# Volta-Interface-SCH_SH2__A.net
KiCad netlist of a schematic drawn in Altium Designer
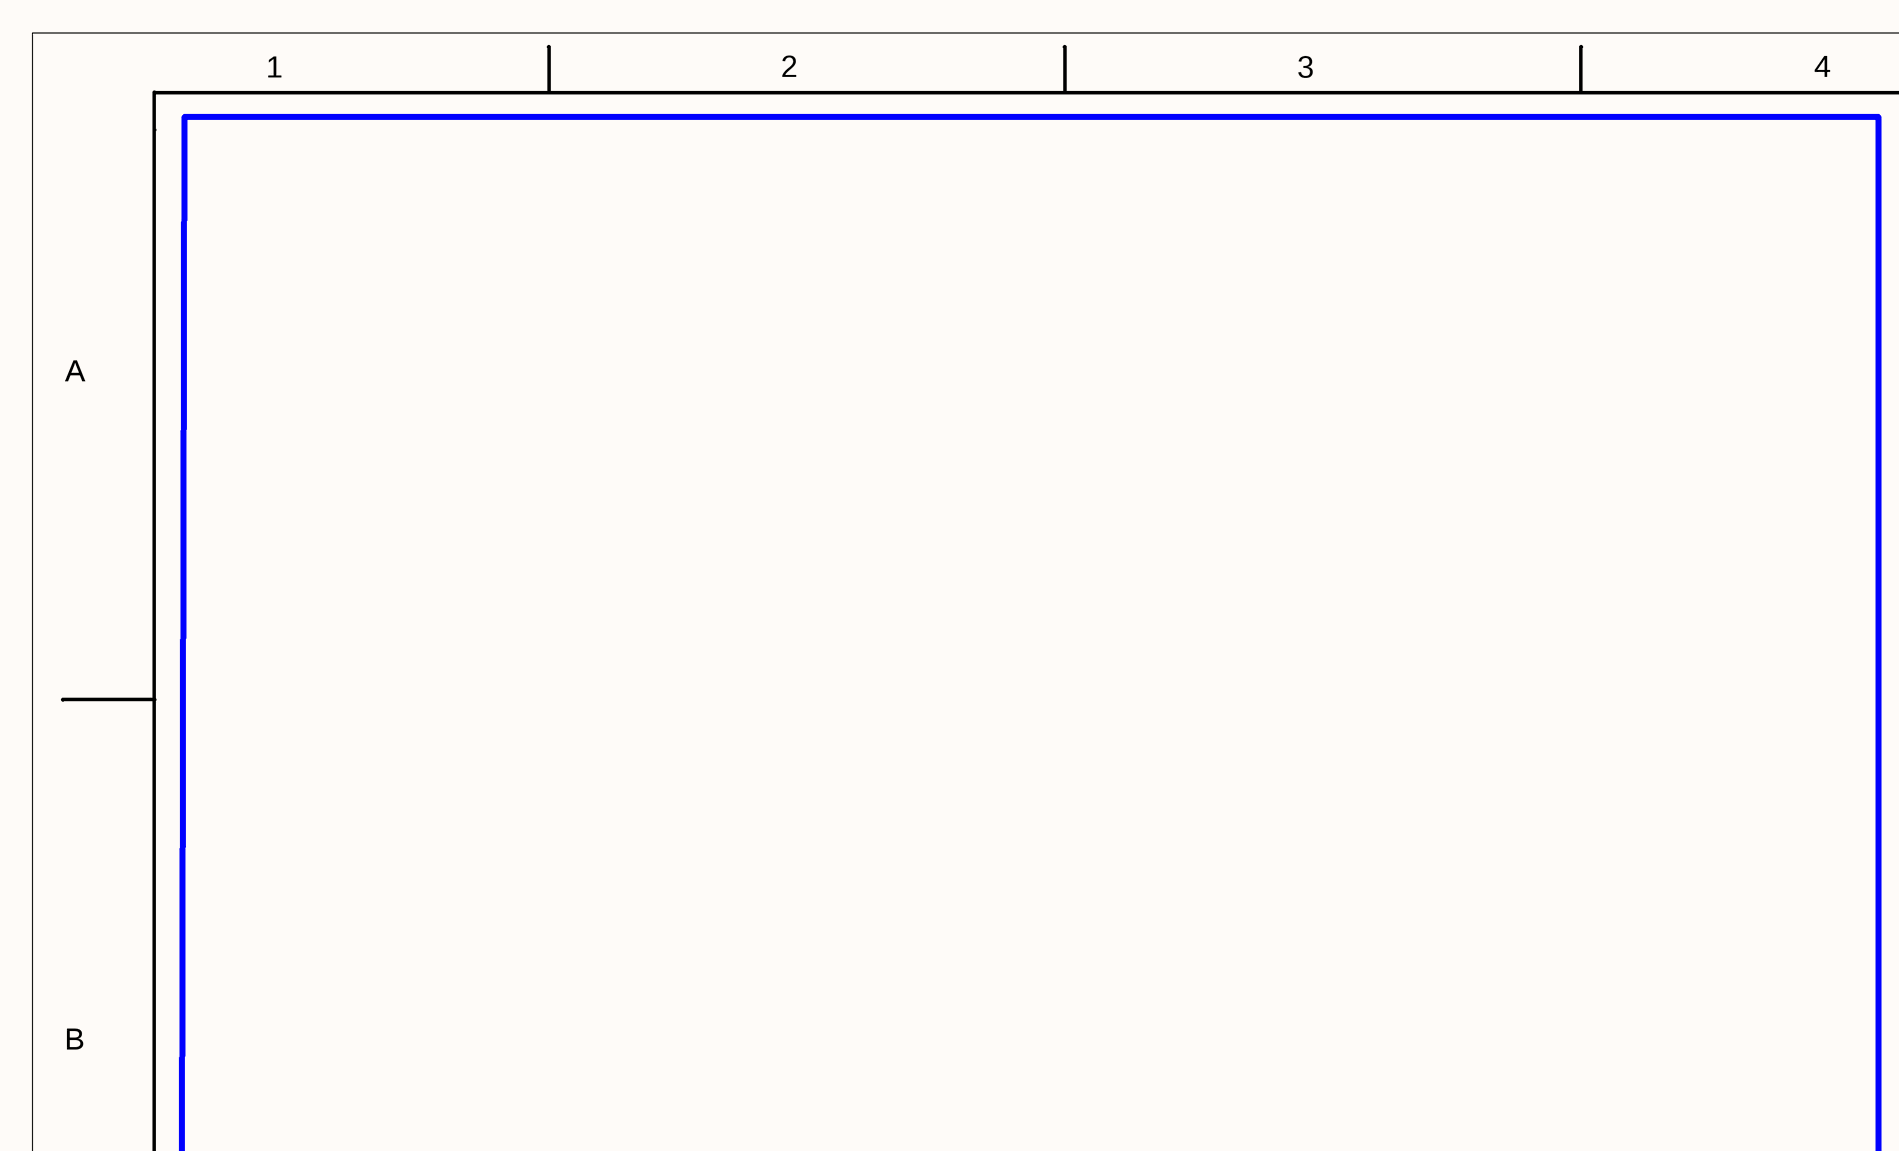
[diagram p0: Volta-Interface-SCH_SH2_(A).SchDoc, top left]
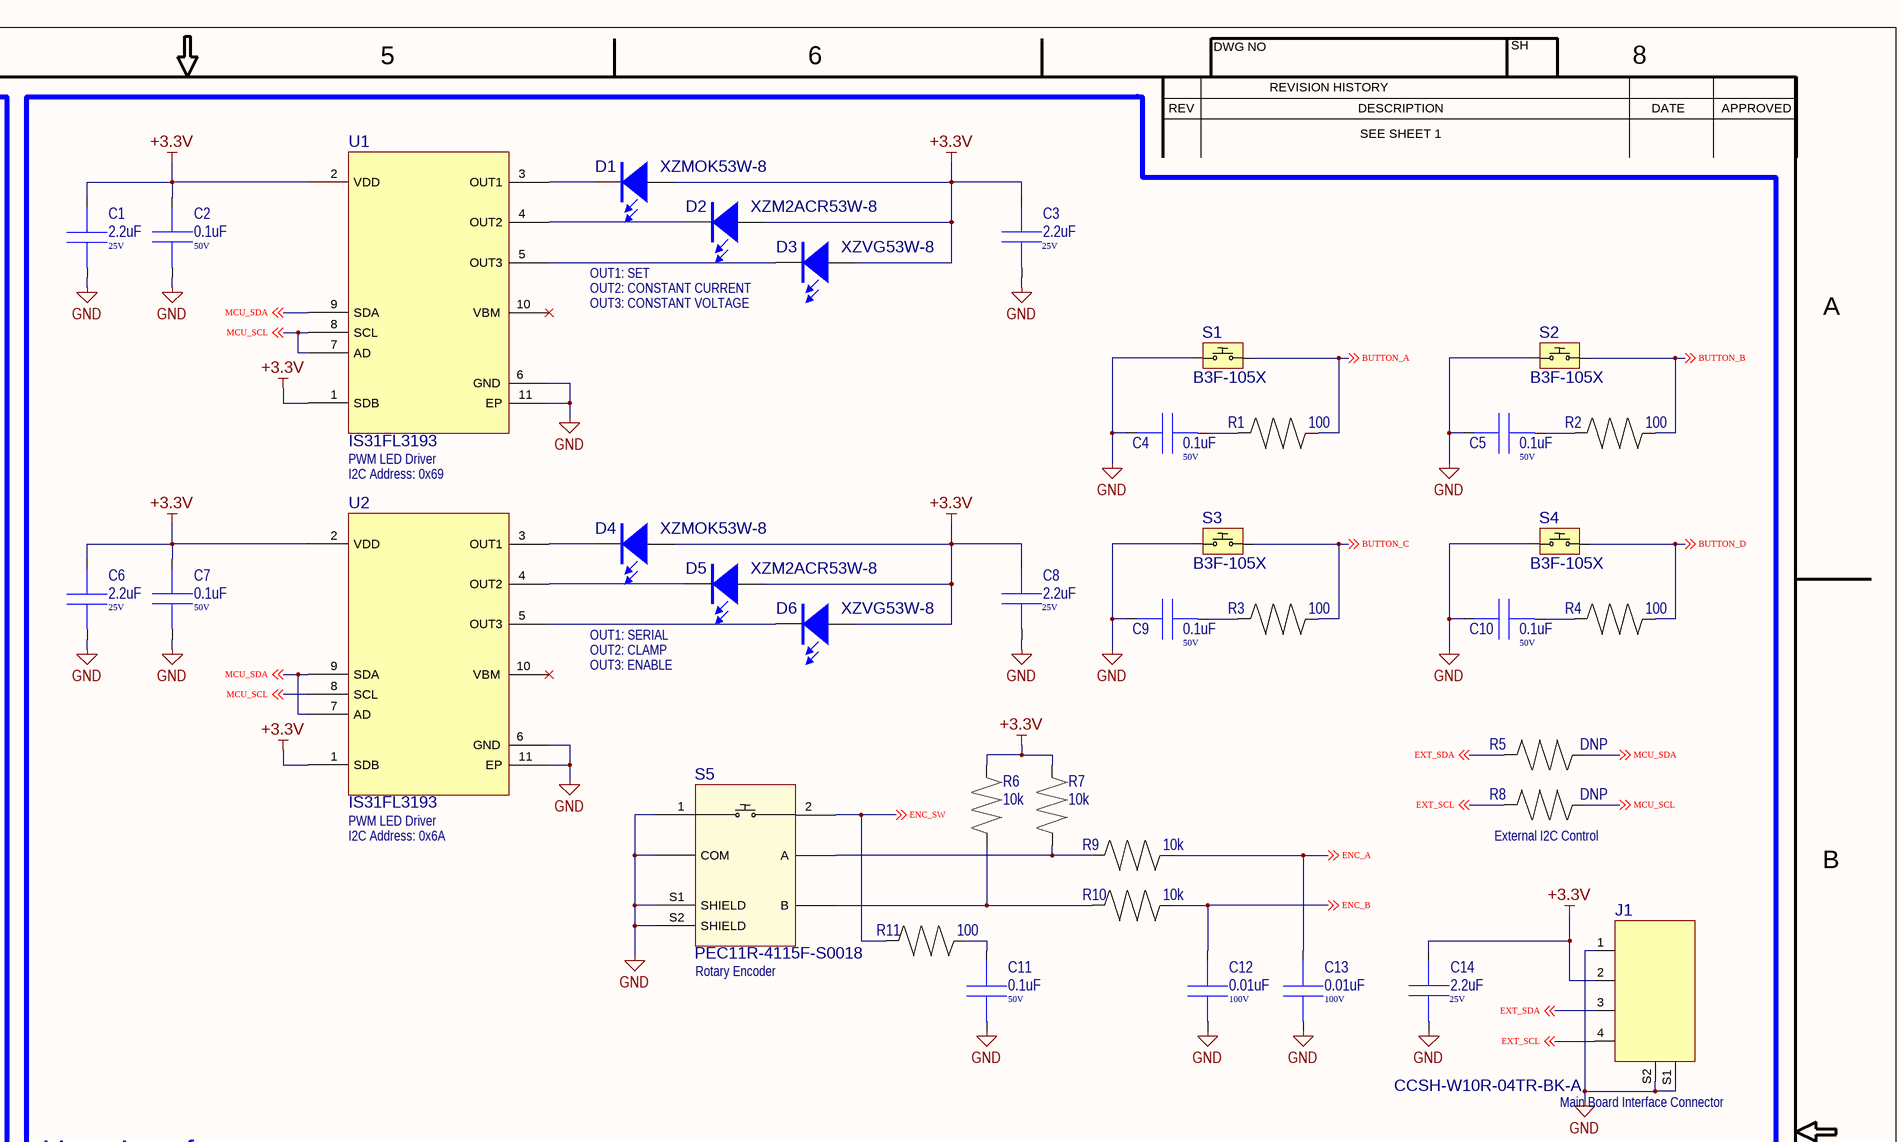
[diagram p1: Volta-Interface-SCH_SH2_(A).SchDoc, top right]
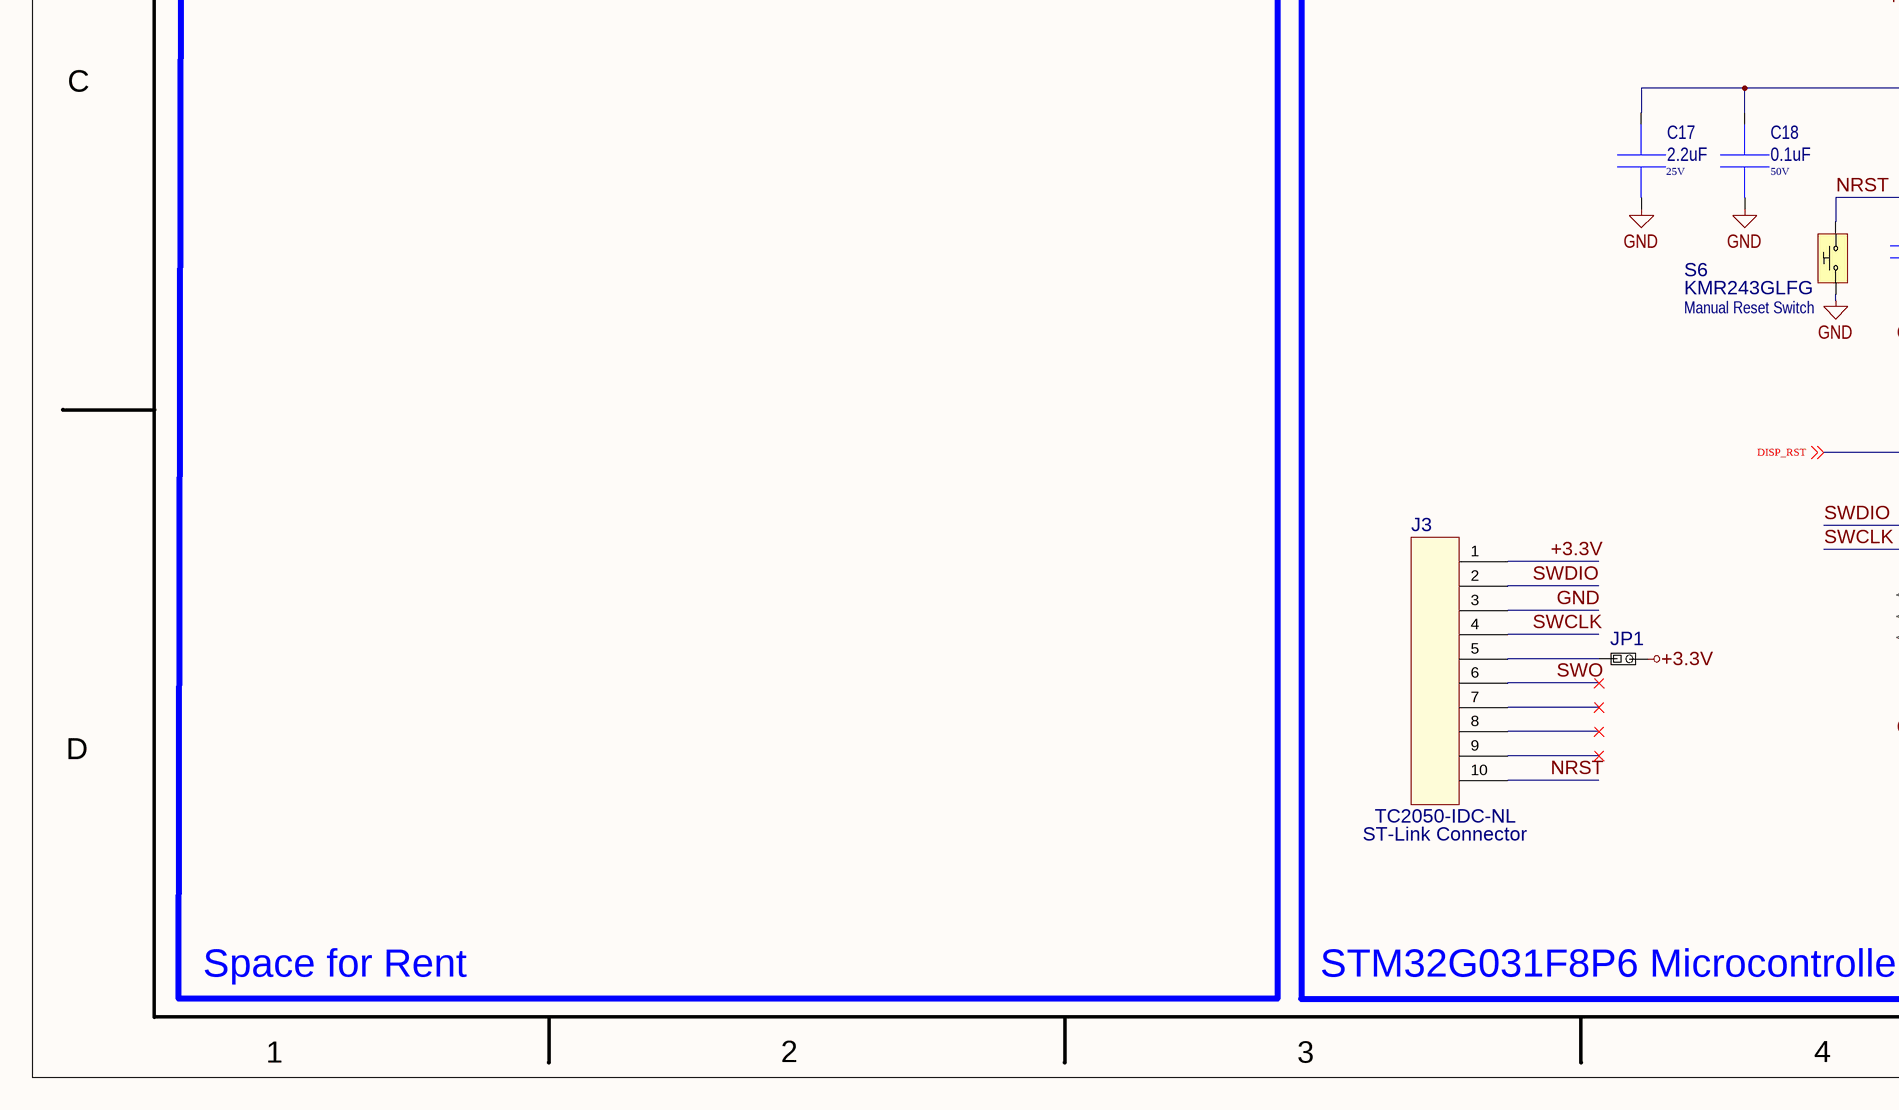
[diagram p2: Volta-Interface-SCH_SH2_(A).SchDoc, bottom left]
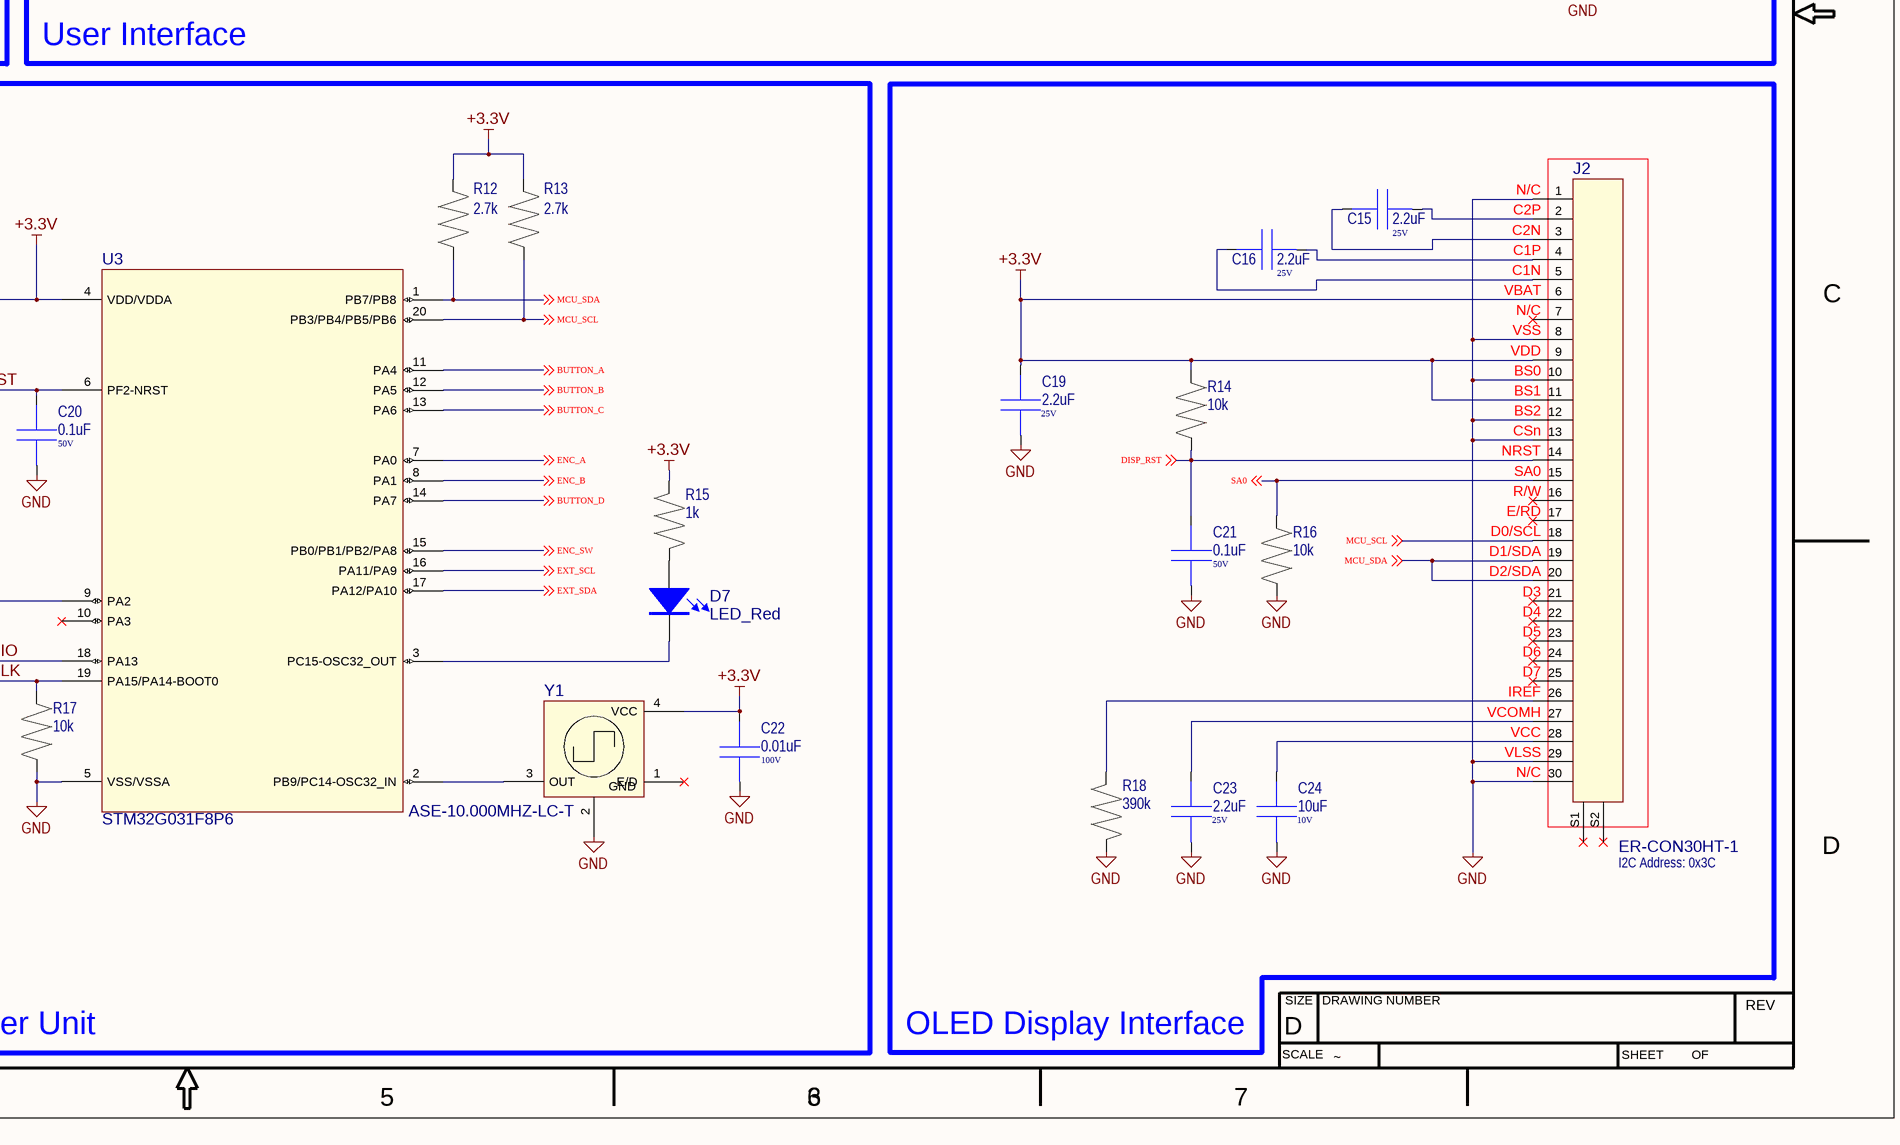
[diagram p3: Volta-Interface-SCH_SH2_(A).SchDoc, bottom right]

(export (version "E")
  (design (tool "Eeschema 10.0.6"))
  (components
    (comp (ref "C1")
      (value "2.2uF")
      (footprint "0402")
      (description "CAP CER 2.2UF 25V X5R 0402")
      (fields
        (field (name "PART NUMBER") "GRM155R61E225KE11D")
        (field (name "MANUFACTURER") "Murata Electronics")
        (field (name "VOLTAGE") "25V")
      )
      (libsource (lib "CAPACITORS") (part "CAP"))
    )
    (comp (ref "C2")
      (value "0.1uF")
      (footprint "0402")
      (description "CAP CER 0.1UF 50V X7R 0402")
      (fields
        (field (name "PART NUMBER") "UMK105B7104KVHF")
        (field (name "MANUFACTURER") "Taiyo Yuden")
        (field (name "VOLTAGE") "50V")
      )
      (libsource (lib "CAPACITORS") (part "CAP"))
    )
    (comp (ref "C3")
      (value "2.2uF")
      (footprint "0402")
      (description "CAP CER 2.2UF 25V X5R 0402")
      (fields
        (field (name "PART NUMBER") "GRM155R61E225KE11D")
        (field (name "MANUFACTURER") "Murata Electronics")
        (field (name "VOLTAGE") "25V")
      )
      (libsource (lib "CAPACITORS") (part "CAP"))
    )
    (comp (ref "C4")
      (value "0.1uF")
      (footprint "0402")
      (description "CAP CER 0.1UF 50V X7R 0402")
      (fields
        (field (name "PART NUMBER") "GRM155R61E225KE11D")
        (field (name "MANUFACTURER") "Taiyo Yuden")
        (field (name "VOLTAGE") "50V")
      )
      (libsource (lib "CAPACITORS") (part "CAP"))
    )
    (comp (ref "C5")
      (value "0.1uF")
      (footprint "0402")
      (description "CAP CER 0.1UF 50V X7R 0402")
      (fields
        (field (name "PART NUMBER") "GRM155R61E225KE11D")
        (field (name "MANUFACTURER") "Taiyo Yuden")
        (field (name "VOLTAGE") "50V")
      )
      (libsource (lib "CAPACITORS") (part "CAP"))
    )
    (comp (ref "C6")
      (value "2.2uF")
      (footprint "0402")
      (description "CAP CER 2.2UF 25V X5R 0402")
      (fields
        (field (name "PART NUMBER") "GRM155R61E225KE11D")
        (field (name "MANUFACTURER") "Murata Electronics")
        (field (name "VOLTAGE") "25V")
      )
      (libsource (lib "CAPACITORS") (part "CAP"))
    )
    (comp (ref "C7")
      (value "0.1uF")
      (footprint "0402")
      (description "CAP CER 0.1UF 50V X7R 0402")
      (fields
        (field (name "PART NUMBER") "UMK105B7104KVHF")
        (field (name "MANUFACTURER") "Taiyo Yuden")
        (field (name "VOLTAGE") "50V")
      )
      (libsource (lib "CAPACITORS") (part "CAP"))
    )
    (comp (ref "C8")
      (value "2.2uF")
      (footprint "0402")
      (description "CAP CER 2.2UF 25V X5R 0402")
      (fields
        (field (name "PART NUMBER") "GRM155R61E225KE11D")
        (field (name "MANUFACTURER") "Murata Electronics")
        (field (name "VOLTAGE") "25V")
      )
      (libsource (lib "CAPACITORS") (part "CAP"))
    )
    (comp (ref "C9")
      (value "0.1uF")
      (footprint "0402")
      (description "CAP CER 0.1UF 50V X7R 0402")
      (fields
        (field (name "PART NUMBER") "GRM155R61E225KE11D")
        (field (name "MANUFACTURER") "Taiyo Yuden")
        (field (name "VOLTAGE") "50V")
      )
      (libsource (lib "CAPACITORS") (part "CAP"))
    )
    (comp (ref "C10")
      (value "0.1uF")
      (footprint "0402")
      (description "CAP CER 0.1UF 50V X7R 0402")
      (fields
        (field (name "PART NUMBER") "GRM155R61E225KE11D")
        (field (name "MANUFACTURER") "Taiyo Yuden")
        (field (name "VOLTAGE") "50V")
      )
      (libsource (lib "CAPACITORS") (part "CAP"))
    )
    (comp (ref "C11")
      (value "0.1uF")
      (footprint "0402")
      (description "CAP CER 0.1UF 50V X7R 0402")
      (fields
        (field (name "PART NUMBER") "GRM155R61E225KE11D")
        (field (name "MANUFACTURER") "Taiyo Yuden")
        (field (name "VOLTAGE") "50V")
      )
      (libsource (lib "CAPACITORS") (part "CAP"))
    )
    (comp (ref "C12")
      (value "0.01uF")
      (footprint "0402")
      (description "CAP CER 0.01UF 100V X7R 0402")
      (fields
        (field (name "PART NUMBER") "HMR105B7103MV-F")
        (field (name "MANUFACTURER") "Taiyo Yuden")
        (field (name "VOLTAGE") "100V")
      )
      (libsource (lib "CAPACITORS") (part "CAP"))
    )
    (comp (ref "C13")
      (value "0.01uF")
      (footprint "0402")
      (description "CAP CER 0.01UF 100V X7R 0402")
      (fields
        (field (name "PART NUMBER") "HMR105B7103MV-F")
        (field (name "MANUFACTURER") "Taiyo Yuden")
        (field (name "VOLTAGE") "100V")
      )
      (libsource (lib "CAPACITORS") (part "CAP"))
    )
    (comp (ref "C14")
      (value "2.2uF")
      (footprint "0402")
      (description "CAP CER 2.2UF 25V X5R 0402")
      (fields
        (field (name "PART NUMBER") "GRM155R61E225KE11D")
        (field (name "MANUFACTURER") "Murata Electronics")
        (field (name "VOLTAGE") "25V")
      )
      (libsource (lib "CAPACITORS") (part "CAP"))
    )
    (comp (ref "C15")
      (value "2.2uF")
      (footprint "0402")
      (description "CAP CER 2.2UF 25V X5R 0402")
      (fields
        (field (name "PART NUMBER") "GRM155R61E225KE11D")
        (field (name "MANUFACTURER") "Murata Electronics")
        (field (name "VOLTAGE") "25V")
      )
      (libsource (lib "CAPACITORS") (part "CAP"))
    )
    (comp (ref "C16")
      (value "2.2uF")
      (footprint "0402")
      (description "CAP CER 2.2UF 25V X5R 0402")
      (fields
        (field (name "PART NUMBER") "GRM155R61E225KE11D")
        (field (name "MANUFACTURER") "Murata Electronics")
        (field (name "VOLTAGE") "25V")
      )
      (libsource (lib "CAPACITORS") (part "CAP"))
    )
    (comp (ref "C17")
      (value "2.2uF")
      (footprint "0402")
      (description "CAP CER 2.2UF 25V X5R 0402")
      (fields
        (field (name "PART NUMBER") "GRM155R61E225KE11D")
        (field (name "MANUFACTURER") "Murata Electronics")
        (field (name "VOLTAGE") "25V")
      )
      (libsource (lib "CAPACITORS") (part "CAP"))
    )
    (comp (ref "C18")
      (value "0.1uF")
      (footprint "0402")
      (description "CAP CER 0.1UF 50V X7R 0402")
      (fields
        (field (name "PART NUMBER") "UMK105B7104KVHF")
        (field (name "MANUFACTURER") "Taiyo Yuden")
        (field (name "VOLTAGE") "50V")
      )
      (libsource (lib "CAPACITORS") (part "CAP"))
    )
    (comp (ref "C19")
      (value "2.2uF")
      (footprint "0402")
      (description "CAP CER 2.2UF 25V X5R 0402")
      (fields
        (field (name "PART NUMBER") "GRM155R61E225KE11D")
        (field (name "MANUFACTURER") "Murata Electronics")
        (field (name "VOLTAGE") "25V")
      )
      (libsource (lib "CAPACITORS") (part "CAP"))
    )
    (comp (ref "C20")
      (value "0.1uF")
      (footprint "0402")
      (description "CAP CER 0.1UF 50V X7R 0402")
      (fields
        (field (name "PART NUMBER") "UMK105B7104KVHF")
        (field (name "MANUFACTURER") "Taiyo Yuden")
        (field (name "VOLTAGE") "50V")
      )
      (libsource (lib "CAPACITORS") (part "CAP"))
    )
    (comp (ref "C21")
      (value "0.1uF")
      (footprint "0402")
      (description "CAP CER 0.1UF 50V X7R 0402")
      (fields
        (field (name "PART NUMBER") "UMK105B7104KVHF")
        (field (name "MANUFACTURER") "Taiyo Yuden")
        (field (name "VOLTAGE") "50V")
      )
      (libsource (lib "CAPACITORS") (part "CAP"))
    )
    (comp (ref "C22")
      (value "0.01uF")
      (footprint "0402")
      (description "CAP CER 0.01UF 100V X7R 0402")
      (fields
        (field (name "PART NUMBER") "HMR105B7103MV-F")
        (field (name "MANUFACTURER") "Taiyo Yuden")
        (field (name "VOLTAGE") "100V")
      )
      (libsource (lib "CAPACITORS") (part "CAP"))
    )
    (comp (ref "C23")
      (value "2.2uF")
      (footprint "0402")
      (description "CAP CER 2.2UF 25V X5R 0402")
      (fields
        (field (name "PART NUMBER") "GRM155R61E225KE11D")
        (field (name "MANUFACTURER") "Murata Electronics")
        (field (name "VOLTAGE") "25V")
      )
      (libsource (lib "CAPACITORS") (part "CAP"))
    )
    (comp (ref "C24")
      (value "10uF")
      (footprint "0402")
      (description "CAP CER 10UF 10V X5R 0402")
      (fields
        (field (name "PART NUMBER") "CL05A106MP8NUB8")
        (field (name "MANUFACTURER") "Samsung Electro-Mechanics")
        (field (name "VOLTAGE") "10V")
      )
      (libsource (lib "CAPACITORS") (part "CAP"))
    )
    (comp (ref "D1")
      (value "XZMOK53W-8")
      (footprint "0603_LED_DOME")
      (description "LED ORANGE CLEAR CHIP SMD")
      (fields (field (name "MANUFACTURER") "SunLED"))
      (libsource (lib "SEMICONDUCTORS") (part "LED"))
    )
    (comp (ref "D2")
      (value "XZM2ACR53W-8")
      (footprint "0603_LED_DOME")
      (description "LED RED CLEAR CHIP SMD")
      (fields (field (name "MANUFACTURER") "SunLED"))
      (libsource (lib "SEMICONDUCTORS") (part "LED"))
    )
    (comp (ref "D3")
      (value "XZVG53W-8")
      (footprint "0603_LED_DOME")
      (description "LED GREEN CLEAR CHIP SMD")
      (fields (field (name "MANUFACTURER") "SunLED"))
      (libsource (lib "SEMICONDUCTORS") (part "LED"))
    )
    (comp (ref "D4")
      (value "XZMOK53W-8")
      (footprint "0603_LED_DOME")
      (description "LED ORANGE CLEAR CHIP SMD")
      (fields (field (name "MANUFACTURER") "SunLED"))
      (libsource (lib "SEMICONDUCTORS") (part "LED"))
    )
    (comp (ref "D5")
      (value "XZM2ACR53W-8")
      (footprint "0603_LED_DOME")
      (description "LED RED CLEAR CHIP SMD")
      (fields (field (name "MANUFACTURER") "SunLED"))
      (libsource (lib "SEMICONDUCTORS") (part "LED"))
    )
    (comp (ref "D6")
      (value "XZVG53W-8")
      (footprint "0603_LED_DOME")
      (description "LED GREEN CLEAR CHIP SMD")
      (fields (field (name "MANUFACTURER") "SunLED"))
      (libsource (lib "SEMICONDUCTORS") (part "LED"))
    )
    (comp (ref "D7")
      (value "LED_Red")
      (footprint "0603_LED_Red")
      (description "LED HE RD 0603")
      (fields (field (name "PART NUMBER") "SM0603HCL") (field (name "MANUFACTURER") "Bivar"))
      (libsource (lib "SEMICONDUCTORS") (part "LED_Red"))
    )
    (comp (ref "J1")
      (value "CCSH-W10R-04TR-BK-A")
      (footprint "CCSH-W10R-04TR-BK-A")
      (description "JST 4 PIN SMT CONN")
      (fields (field (name "MANUFACTURER") "JST"))
      (libsource (lib "ConnectorLib") (part "CCSH-W10R-04TR-BK-A"))
    )
    (comp (ref "J2")
      (value "ER-CON30HT-1")
      (footprint "ER-CON30HT-1")
      (description "30 PINS 0.5 PITCH SMD TOP CONTACT CONN")
      (fields (field (name "MANUFACTURER") "EastRising Technology"))
      (libsource (lib "ConnectorLib") (part "ER-CON30HT-1"))
    )
    (comp (ref "J3")
      (value "TC2050-IDC-NL")
      (footprint "TC2050-IDC-NL-FP")
      (description "CBL PLUG-OF-NAILS 10-PIN")
      (fields (field (name "MANUFACTURER") "Tag-Connect LLC"))
      (libsource (lib "Connectors") (part "TC2050-IDC-NL"))
    )
    (comp (ref "JP1")
      (value "Solder Jumper")
      (footprint "SOLDER JUMPER")
      (description "Solder Jumper Single 0.5mm Pitch")
      (libsource (lib "ConnectorLib") (part "SolderJumper_Single"))
    )
    (comp (ref "R1")
      (value "100")
      (footprint "0402")
      (description "RES SMD 100 OHM 1% 1/16W 0402")
      (fields (field (name "PART NUMBER") "ERJ-2RKF1000X") (field (name "MANUFACTURER") "Panasonic"))
      (libsource (lib "RESISTORS") (part "RES"))
    )
    (comp (ref "R2")
      (value "100")
      (footprint "0402")
      (description "RES SMD 100 OHM 1% 1/16W 0402")
      (fields (field (name "PART NUMBER") "ERJ-2RKF1000X") (field (name "MANUFACTURER") "Panasonic"))
      (libsource (lib "RESISTORS") (part "RES"))
    )
    (comp (ref "R3")
      (value "100")
      (footprint "0402")
      (description "RES SMD 100 OHM 1% 1/16W 0402")
      (fields (field (name "PART NUMBER") "ERJ-2RKF1000X") (field (name "MANUFACTURER") "Panasonic"))
      (libsource (lib "RESISTORS") (part "RES"))
    )
    (comp (ref "R4")
      (value "100")
      (footprint "0402")
      (description "RES SMD 100 OHM 1% 1/16W 0402")
      (fields (field (name "PART NUMBER") "ERJ-2RKF1000X") (field (name "MANUFACTURER") "Panasonic"))
      (libsource (lib "RESISTORS") (part "RES"))
    )
    (comp (ref "R5")
      (value "DNP")
      (footprint "0402")
      (description "RES 0 OHM JUMPER 1/16W 0402")
      (fields (field (name "PART NUMBER") "CRCW04020000Z0EDC") (field (name "MANUFACTURER") "Vishay / Dale"))
      (libsource (lib "RESISTORS") (part "RES"))
    )
    (comp (ref "R6")
      (value "10k")
      (footprint "0402")
      (description "RES SMD 10K OHM 1% 1/16W 0402")
      (fields (field (name "PART NUMBER") "CR0402-FX-1002GLF") (field (name "MANUFACTURER") "Bourns"))
      (libsource (lib "RESISTORS") (part "RES"))
    )
    (comp (ref "R7")
      (value "10k")
      (footprint "0402")
      (description "RES SMD 10K OHM 1% 1/16W 0402")
      (fields (field (name "PART NUMBER") "CR0402-FX-1002GLF") (field (name "MANUFACTURER") "Bourns"))
      (libsource (lib "RESISTORS") (part "RES"))
    )
    (comp (ref "R8")
      (value "DNP")
      (footprint "0402")
      (description "RES 0 OHM JUMPER 1/16W 0402")
      (fields (field (name "PART NUMBER") "CRCW04020000Z0EDC") (field (name "MANUFACTURER") "Vishay / Dale"))
      (libsource (lib "RESISTORS") (part "RES"))
    )
    (comp (ref "R9")
      (value "10k")
      (footprint "0402")
      (description "RES SMD 10K OHM 1% 1/16W 0402")
      (fields (field (name "PART NUMBER") "CR0402-FX-1002GLF") (field (name "MANUFACTURER") "Bourns"))
      (libsource (lib "RESISTORS") (part "RES"))
    )
    (comp (ref "R10")
      (value "10k")
      (footprint "0402")
      (description "RES SMD 10K OHM 1% 1/16W 0402")
      (fields (field (name "PART NUMBER") "CR0402-FX-1002GLF") (field (name "MANUFACTURER") "Bourns"))
      (libsource (lib "RESISTORS") (part "RES"))
    )
    (comp (ref "R11")
      (value "100")
      (footprint "0402")
      (description "RES SMD 100 OHM 1% 1/16W 0402")
      (fields (field (name "PART NUMBER") "ERJ-2RKF1000X") (field (name "MANUFACTURER") "Panasonic"))
      (libsource (lib "RESISTORS") (part "RES"))
    )
    (comp (ref "R12")
      (value "2.7k")
      (footprint "0402")
      (description "RES SMD 2.7K OHM 1% 1/10W 0402")
      (fields (field (name "PART NUMBER") "ERJ-2RKF2701X") (field (name "MANUFACTURER") "Panasonic"))
      (libsource (lib "RESISTORS") (part "RES"))
    )
    (comp (ref "R13")
      (value "2.7k")
      (footprint "0402")
      (description "RES SMD 2.7K OHM 1% 1/10W 0402")
      (fields (field (name "PART NUMBER") "ERJ-2RKF2701X") (field (name "MANUFACTURER") "Panasonic"))
      (libsource (lib "RESISTORS") (part "RES"))
    )
    (comp (ref "R14")
      (value "10k")
      (footprint "0402")
      (description "RES SMD 10K OHM 1% 1/16W 0402")
      (fields (field (name "PART NUMBER") "CR0402-FX-1002GLF") (field (name "MANUFACTURER") "Bourns"))
      (libsource (lib "RESISTORS") (part "RES"))
    )
    (comp (ref "R15")
      (value "1k")
      (footprint "0402")
      (description "RES 1K OHM 1% 1/16W 0402")
      (fields (field (name "PART NUMBER") "CR0402AFX-1001GLF") (field (name "MANUFACTURER") "Bourns"))
      (libsource (lib "RESISTORS") (part "RES"))
    )
    (comp (ref "R16")
      (value "10k")
      (footprint "0402")
      (description "RES SMD 10K OHM 1% 1/16W 0402")
      (fields (field (name "PART NUMBER") "CR0402-FX-1002GLF") (field (name "MANUFACTURER") "Bourns"))
      (libsource (lib "RESISTORS") (part "RES"))
    )
    (comp (ref "R17")
      (value "10k")
      (footprint "0402")
      (description "RES SMD 10K OHM 1% 1/16W 0402")
      (fields (field (name "PART NUMBER") "CR0402-FX-1002GLF") (field (name "MANUFACTURER") "Bourns"))
      (libsource (lib "RESISTORS") (part "RES"))
    )
    (comp (ref "R18")
      (value "390k")
      (footprint "0402")
      (description "RES SMD 390K OHM 1% 1/16W 0402")
      (fields (field (name "PART NUMBER") "CR0402-FX-3903GLF") (field (name "MANUFACTURER") "Bourns Inc."))
      (libsource (lib "RESISTORS") (part "RES"))
    )
    (comp (ref "S1")
      (value "B3F-105X")
      (footprint "B3F-105X")
      (description "SWITCH TACTILE SPST-NO 0.05A 24V")
      (fields (field (name "MANUFACTURER") "Omron Electronics Inc-EMC Div"))
      (libsource (lib "SwitchesLib") (part "B3F-105X"))
    )
    (comp (ref "S2")
      (value "B3F-105X")
      (footprint "B3F-105X")
      (description "SWITCH TACTILE SPST-NO 0.05A 24V")
      (fields (field (name "MANUFACTURER") "Omron Electronics Inc-EMC Div"))
      (libsource (lib "SwitchesLib") (part "B3F-105X"))
    )
    (comp (ref "S3")
      (value "B3F-105X")
      (footprint "B3F-105X")
      (description "SWITCH TACTILE SPST-NO 0.05A 24V")
      (fields (field (name "MANUFACTURER") "Omron Electronics Inc-EMC Div"))
      (libsource (lib "SwitchesLib") (part "B3F-105X"))
    )
    (comp (ref "S4")
      (value "B3F-105X")
      (footprint "B3F-105X")
      (description "SWITCH TACTILE SPST-NO 0.05A 24V")
      (fields (field (name "MANUFACTURER") "Omron Electronics Inc-EMC Div"))
      (libsource (lib "SwitchesLib") (part "B3F-105X"))
    )
    (comp (ref "S5")
      (value "PEC11R-4115F-S0018")
      (footprint "PEC11R-4xxxF-Sxxxx")
      (description "ROTARY ENCODER MECHANICAL XXPPR")
      (fields (field (name "MANUFACTURER") "Bourns"))
      (libsource (lib "SwitchesLib") (part "PEC11R-4xxxF-Sxxxx"))
    )
    (comp (ref "S6")
      (value "KMR243GLFG")
      (footprint "KMR 2 Series")
      (description "SWITCH TACTILE SPST-NO 0.01A 32V")
      (fields (field (name "MANUFACTURER") "C&K"))
      (libsource (lib "SwitchesLib") (part "KMR 2 Series"))
    )
    (comp (ref "U1")
      (value "IS31FL3193")
      (footprint "DFN-10")
      (description "IC LED DRIVER LINEAR 42MA 10DFN")
      (fields
        (field (name "MANUFACTURER") "Lumissil Microsystems")
        (field (name "PART NUMBER") "IS31FL3193-DLS2-TR")
      )
      (libsource (lib "LED Drivers") (part "IS31FL3193"))
    )
    (comp (ref "U2")
      (value "IS31FL3193")
      (footprint "DFN-10")
      (description "IC LED DRIVER LINEAR 42MA 10DFN")
      (fields
        (field (name "MANUFACTURER") "Lumissil Microsystems")
        (field (name "PART NUMBER") "IS31FL3193-DLS2-TR")
      )
      (libsource (lib "LED Drivers") (part "IS31FL3193"))
    )
    (comp (ref "U3")
      (value "STM32G031F8P6")
      (footprint "TSSOP-20")
      (description "IC MCU 32BIT 64KB FLASH 20TSSOP")
      (fields (field (name "MANUFACTURER") "STMicroelectronics"))
      (libsource (lib "MicrocontrollerUnits") (part "STM32G031FxP6"))
    )
    (comp (ref "Y1")
      (value "ASE-10.000MHZ-LC-T")
      (footprint "ASE-XXXXX-X-X-X")
      (description "OSC XO 10.000MHZ CMOS SMD")
      (fields (field (name "MANUFACTURER") "Abracon"))
      (libsource (lib "Oscillators") (part "ASE-XXXXX-MHZ-X-X"))
    )
  )
  (nets
    (net (code "1") (name "+3.3V") (class "Default")
      (node (ref "C1") (pin "2") (pinfunction "2_2") (pintype "passive"))
      (node (ref "C14") (pin "2") (pinfunction "2_2") (pintype "passive"))
      (node (ref "C17") (pin "2") (pinfunction "2_2") (pintype "passive"))
      (node (ref "C18") (pin "2") (pinfunction "2_2") (pintype "passive"))
      (node (ref "C19") (pin "2") (pinfunction "2_2") (pintype "passive"))
      (node (ref "C2") (pin "2") (pinfunction "2_2") (pintype "passive"))
      (node (ref "C22") (pin "2") (pinfunction "2_2") (pintype "passive"))
      (node (ref "C3") (pin "2") (pinfunction "2_2") (pintype "passive"))
      (node (ref "C6") (pin "2") (pinfunction "2_2") (pintype "passive"))
      (node (ref "C7") (pin "2") (pinfunction "2_2") (pintype "passive"))
      (node (ref "C8") (pin "2") (pinfunction "2_2") (pintype "passive"))
      (node (ref "D1") (pin "1") (pinfunction "A_1") (pintype "passive"))
      (node (ref "D2") (pin "1") (pinfunction "A_1") (pintype "passive"))
      (node (ref "D3") (pin "1") (pinfunction "A_1") (pintype "passive"))
      (node (ref "D4") (pin "1") (pinfunction "A_1") (pintype "passive"))
      (node (ref "D5") (pin "1") (pinfunction "A_1") (pintype "passive"))
      (node (ref "D6") (pin "1") (pinfunction "A_1") (pintype "passive"))
      (node (ref "J1") (pin "2") (pinfunction "2_2") (pintype "passive"))
      (node (ref "J2") (pin "11") (pinfunction "11_11") (pintype "passive"))
      (node (ref "J2") (pin "6") (pinfunction "6_6") (pintype "passive"))
      (node (ref "J2") (pin "9") (pinfunction "9_9") (pintype "passive"))
      (node (ref "J3") (pin "1") (pinfunction "1_1") (pintype "passive"))
      (node (ref "JP1") (pin "2") (pinfunction "2_2") (pintype "passive"))
      (node (ref "R12") (pin "2") (pinfunction "2_2") (pintype "passive"))
      (node (ref "R13") (pin "2") (pinfunction "2_2") (pintype "passive"))
      (node (ref "R14") (pin "1") (pinfunction "1_1") (pintype "passive"))
      (node (ref "R15") (pin "2") (pinfunction "2_2") (pintype "passive"))
      (node (ref "R6") (pin "1") (pinfunction "1_1") (pintype "passive"))
      (node (ref "R7") (pin "1") (pinfunction "1_1") (pintype "passive"))
      (node (ref "U1") (pin "1") (pinfunction "SDB_1") (pintype "passive"))
      (node (ref "U1") (pin "2") (pinfunction "VDD_2") (pintype "passive"))
      (node (ref "U2") (pin "1") (pinfunction "SDB_1") (pintype "passive"))
      (node (ref "U2") (pin "2") (pinfunction "VDD_2") (pintype "passive"))
      (node (ref "U3") (pin "4") (pinfunction "VDD/VDDA_4") (pintype "power_in"))
      (node (ref "Y1") (pin "4") (pinfunction "VCC_4") (pintype "power_in"))
    )
    (net (code "2") (name "/NRST") (class "Default")
      (node (ref "C20") (pin "2") (pinfunction "2_2") (pintype "passive"))
      (node (ref "J3") (pin "10") (pinfunction "10_10") (pintype "passive"))
      (node (ref "S6") (pin "2") (pinfunction "2_2") (pintype "passive"))
      (node (ref "U3") (pin "6") (pinfunction "PF2-NRST_6") (pintype "passive"))
    )
    (net (code "3") (name "/SWCLK") (class "Default")
      (node (ref "J3") (pin "4") (pinfunction "4_4") (pintype "passive"))
      (node (ref "R17") (pin "1") (pinfunction "1_1") (pintype "passive"))
      (node (ref "U3") (pin "19") (pinfunction "PA15/PA14-BOOT0_19") (pintype "passive"))
    )
    (net (code "4") (name "/SWDIO") (class "Default")
      (node (ref "J3") (pin "2") (pinfunction "2_2") (pintype "passive"))
      (node (ref "U3") (pin "18") (pinfunction "PA13_18") (pintype "bidirectional"))
    )
    (net (code "5") (name "/SWO") (class "Default")
      (node (ref "J3") (pin "6") (pinfunction "6_6") (pintype "passive+no_connect"))
    )
    (net (code "6") (name "BUTTON_A") (class "Default")
      (node (ref "R1") (pin "2") (pinfunction "2_2") (pintype "passive"))
      (node (ref "S1") (pin "2") (pinfunction "2_2") (pintype "passive"))
      (node (ref "U3") (pin "11") (pinfunction "PA4_11") (pintype "bidirectional"))
    )
    (net (code "7") (name "BUTTON_B") (class "Default")
      (node (ref "R2") (pin "2") (pinfunction "2_2") (pintype "passive"))
      (node (ref "S2") (pin "2") (pinfunction "2_2") (pintype "passive"))
      (node (ref "U3") (pin "12") (pinfunction "PA5_12") (pintype "bidirectional"))
    )
    (net (code "8") (name "BUTTON_C") (class "Default")
      (node (ref "R3") (pin "2") (pinfunction "2_2") (pintype "passive"))
      (node (ref "S3") (pin "2") (pinfunction "2_2") (pintype "passive"))
      (node (ref "U3") (pin "13") (pinfunction "PA6_13") (pintype "bidirectional"))
    )
    (net (code "9") (name "BUTTON_D") (class "Default")
      (node (ref "R4") (pin "2") (pinfunction "2_2") (pintype "passive"))
      (node (ref "S4") (pin "2") (pinfunction "2_2") (pintype "passive"))
      (node (ref "U3") (pin "14") (pinfunction "PA7_14") (pintype "bidirectional"))
    )
    (net (code "10") (name "DISP_RST") (class "Default")
      (node (ref "C21") (pin "2") (pinfunction "2_2") (pintype "passive"))
      (node (ref "J2") (pin "14") (pinfunction "14_14") (pintype "passive"))
      (node (ref "R14") (pin "2") (pinfunction "2_2") (pintype "passive"))
      (node (ref "U3") (pin "9") (pinfunction "PA2_9") (pintype "bidirectional"))
    )
    (net (code "11") (name "ENC_A") (class "Default")
      (node (ref "C13") (pin "2") (pinfunction "2_2") (pintype "passive"))
      (node (ref "R9") (pin "2") (pinfunction "2_2") (pintype "passive"))
      (node (ref "U3") (pin "7") (pinfunction "PA0_7") (pintype "bidirectional"))
    )
    (net (code "12") (name "ENC_B") (class "Default")
      (node (ref "C12") (pin "2") (pinfunction "2_2") (pintype "passive"))
      (node (ref "R10") (pin "2") (pinfunction "2_2") (pintype "passive"))
      (node (ref "U3") (pin "8") (pinfunction "PA1_8") (pintype "bidirectional"))
    )
    (net (code "13") (name "ENC_SW") (class "Default")
      (node (ref "R11") (pin "1") (pinfunction "1_1") (pintype "passive"))
      (node (ref "S5") (pin "2") (pinfunction "2_2") (pintype "passive"))
      (node (ref "U3") (pin "15") (pinfunction "PB0/PB1/PB2/PA8_15") (pintype "bidirectional"))
    )
    (net (code "14") (name "EXT_SCL") (class "Default")
      (node (ref "J1") (pin "4") (pinfunction "4_4") (pintype "passive"))
      (node (ref "R8") (pin "2") (pinfunction "2_2") (pintype "passive"))
      (node (ref "U3") (pin "16") (pinfunction "PA11/PA9_16") (pintype "bidirectional"))
    )
    (net (code "15") (name "EXT_SDA") (class "Default")
      (node (ref "J1") (pin "3") (pinfunction "3_3") (pintype "passive"))
      (node (ref "R5") (pin "2") (pinfunction "2_2") (pintype "passive"))
      (node (ref "U3") (pin "17") (pinfunction "PA12/PA10_17") (pintype "bidirectional"))
    )
    (net (code "16") (name "GND") (class "Default")
      (node (ref "C1") (pin "1") (pinfunction "1_1") (pintype "passive"))
      (node (ref "C10") (pin "2") (pinfunction "2_2") (pintype "passive"))
      (node (ref "C11") (pin "1") (pinfunction "1_1") (pintype "passive"))
      (node (ref "C12") (pin "1") (pinfunction "1_1") (pintype "passive"))
      (node (ref "C13") (pin "1") (pinfunction "1_1") (pintype "passive"))
      (node (ref "C14") (pin "1") (pinfunction "1_1") (pintype "passive"))
      (node (ref "C17") (pin "1") (pinfunction "1_1") (pintype "passive"))
      (node (ref "C18") (pin "1") (pinfunction "1_1") (pintype "passive"))
      (node (ref "C19") (pin "1") (pinfunction "1_1") (pintype "passive"))
      (node (ref "C2") (pin "1") (pinfunction "1_1") (pintype "passive"))
      (node (ref "C20") (pin "1") (pinfunction "1_1") (pintype "passive"))
      (node (ref "C21") (pin "1") (pinfunction "1_1") (pintype "passive"))
      (node (ref "C22") (pin "1") (pinfunction "1_1") (pintype "passive"))
      (node (ref "C23") (pin "1") (pinfunction "1_1") (pintype "passive"))
      (node (ref "C24") (pin "1") (pinfunction "1_1") (pintype "passive"))
      (node (ref "C3") (pin "1") (pinfunction "1_1") (pintype "passive"))
      (node (ref "C4") (pin "2") (pinfunction "2_2") (pintype "passive"))
      (node (ref "C5") (pin "2") (pinfunction "2_2") (pintype "passive"))
      (node (ref "C6") (pin "1") (pinfunction "1_1") (pintype "passive"))
      (node (ref "C7") (pin "1") (pinfunction "1_1") (pintype "passive"))
      (node (ref "C8") (pin "1") (pinfunction "1_1") (pintype "passive"))
      (node (ref "C9") (pin "2") (pinfunction "2_2") (pintype "passive"))
      (node (ref "J1") (pin "1") (pinfunction "1_1") (pintype "passive"))
      (node (ref "J1") (pin "S1") (pinfunction "S1_S1") (pintype "passive"))
      (node (ref "J1") (pin "S2") (pinfunction "S2_S2") (pintype "passive"))
      (node (ref "J2") (pin "1") (pinfunction "1_1") (pintype "passive"))
      (node (ref "J2") (pin "10") (pinfunction "10_10") (pintype "passive"))
      (node (ref "J2") (pin "12") (pinfunction "12_12") (pintype "passive"))
      (node (ref "J2") (pin "13") (pinfunction "13_13") (pintype "passive"))
      (node (ref "J2") (pin "29") (pinfunction "29_29") (pintype "passive"))
      (node (ref "J2") (pin "30") (pinfunction "30_30") (pintype "passive"))
      (node (ref "J2") (pin "8") (pinfunction "8_8") (pintype "passive"))
      (node (ref "J3") (pin "3") (pinfunction "3_3") (pintype "passive"))
      (node (ref "R16") (pin "2") (pinfunction "2_2") (pintype "passive"))
      (node (ref "R17") (pin "2") (pinfunction "2_2") (pintype "passive"))
      (node (ref "R18") (pin "1") (pinfunction "1_1") (pintype "passive"))
      (node (ref "S1") (pin "1") (pinfunction "1_1") (pintype "passive"))
      (node (ref "S2") (pin "1") (pinfunction "1_1") (pintype "passive"))
      (node (ref "S3") (pin "1") (pinfunction "1_1") (pintype "passive"))
      (node (ref "S4") (pin "1") (pinfunction "1_1") (pintype "passive"))
      (node (ref "S5") (pin "1") (pinfunction "1_1") (pintype "passive"))
      (node (ref "S5") (pin "COM") (pinfunction "COM_COM") (pintype "passive"))
      (node (ref "S5") (pin "S1") (pinfunction "SHIELD_S1") (pintype "passive"))
      (node (ref "S5") (pin "S2") (pinfunction "SHIELD_S2") (pintype "passive"))
      (node (ref "S6") (pin "1") (pinfunction "1_1") (pintype "passive"))
      (node (ref "U1") (pin "11") (pinfunction "EP_11") (pintype "passive"))
      (node (ref "U1") (pin "6") (pinfunction "GND_6") (pintype "passive"))
      (node (ref "U2") (pin "11") (pinfunction "EP_11") (pintype "passive"))
      (node (ref "U2") (pin "6") (pinfunction "GND_6") (pintype "passive"))
      (node (ref "U3") (pin "5") (pinfunction "VSS/VSSA_5") (pintype "power_in"))
      (node (ref "Y1") (pin "2") (pinfunction "GND_2") (pintype "passive"))
    )
    (net (code "17") (name "MCU_SCL") (class "Default")
      (node (ref "J2") (pin "18") (pinfunction "18_18") (pintype "passive"))
      (node (ref "R13") (pin "1") (pinfunction "1_1") (pintype "passive"))
      (node (ref "R8") (pin "1") (pinfunction "1_1") (pintype "passive"))
      (node (ref "U1") (pin "7") (pinfunction "AD_7") (pintype "passive"))
      (node (ref "U1") (pin "8") (pinfunction "SCL_8") (pintype "passive"))
      (node (ref "U2") (pin "8") (pinfunction "SCL_8") (pintype "passive"))
      (node (ref "U3") (pin "20") (pinfunction "PB3/PB4/PB5/PB6_20") (pintype "bidirectional"))
    )
    (net (code "18") (name "MCU_SDA") (class "Default")
      (node (ref "J2") (pin "19") (pinfunction "19_19") (pintype "passive"))
      (node (ref "J2") (pin "20") (pinfunction "20_20") (pintype "passive"))
      (node (ref "R12") (pin "1") (pinfunction "1_1") (pintype "passive"))
      (node (ref "R5") (pin "1") (pinfunction "1_1") (pintype "passive"))
      (node (ref "U1") (pin "9") (pinfunction "SDA_9") (pintype "passive"))
      (node (ref "U2") (pin "7") (pinfunction "AD_7") (pintype "passive"))
      (node (ref "U2") (pin "9") (pinfunction "SDA_9") (pintype "passive"))
      (node (ref "U3") (pin "1") (pinfunction "PB7/PB8_1") (pintype "bidirectional"))
    )
    (net (code "19") (name "Net-(C4-Pad1)") (class "Default")
      (node (ref "C4") (pin "1") (pinfunction "1_1") (pintype "passive"))
      (node (ref "R1") (pin "1") (pinfunction "1_1") (pintype "passive"))
    )
    (net (code "20") (name "Net-(C5-Pad1)") (class "Default")
      (node (ref "C5") (pin "1") (pinfunction "1_1") (pintype "passive"))
      (node (ref "R2") (pin "1") (pinfunction "1_1") (pintype "passive"))
    )
    (net (code "21") (name "Net-(C9-Pad1)") (class "Default")
      (node (ref "C9") (pin "1") (pinfunction "1_1") (pintype "passive"))
      (node (ref "R3") (pin "1") (pinfunction "1_1") (pintype "passive"))
    )
    (net (code "22") (name "Net-(C10-Pad1)") (class "Default")
      (node (ref "C10") (pin "1") (pinfunction "1_1") (pintype "passive"))
      (node (ref "R4") (pin "1") (pinfunction "1_1") (pintype "passive"))
    )
    (net (code "23") (name "Net-(C11-Pad2)") (class "Default")
      (node (ref "C11") (pin "2") (pinfunction "2_2") (pintype "passive"))
      (node (ref "R11") (pin "2") (pinfunction "2_2") (pintype "passive"))
    )
    (net (code "24") (name "Net-(C15-Pad1)") (class "Default")
      (node (ref "C15") (pin "1") (pinfunction "1_1") (pintype "passive"))
      (node (ref "J2") (pin "2") (pinfunction "2_2") (pintype "passive"))
    )
    (net (code "25") (name "Net-(C15-Pad2)") (class "Default")
      (node (ref "C15") (pin "2") (pinfunction "2_2") (pintype "passive"))
      (node (ref "J2") (pin "3") (pinfunction "3_3") (pintype "passive"))
    )
    (net (code "26") (name "Net-(C16-Pad1)") (class "Default")
      (node (ref "C16") (pin "1") (pinfunction "1_1") (pintype "passive"))
      (node (ref "J2") (pin "4") (pinfunction "4_4") (pintype "passive"))
    )
    (net (code "27") (name "Net-(C16-Pad2)") (class "Default")
      (node (ref "C16") (pin "2") (pinfunction "2_2") (pintype "passive"))
      (node (ref "J2") (pin "5") (pinfunction "5_5") (pintype "passive"))
    )
    (net (code "28") (name "Net-(C23-Pad2)") (class "Default")
      (node (ref "C23") (pin "2") (pinfunction "2_2") (pintype "passive"))
      (node (ref "J2") (pin "27") (pinfunction "27_27") (pintype "passive"))
    )
    (net (code "29") (name "Net-(C24-Pad2)") (class "Default")
      (node (ref "C24") (pin "2") (pinfunction "2_2") (pintype "passive"))
      (node (ref "J2") (pin "28") (pinfunction "28_28") (pintype "passive"))
    )
    (net (code "30") (name "Net-(D1-K)") (class "Default")
      (node (ref "D1") (pin "2") (pinfunction "K_2") (pintype "passive"))
      (node (ref "U1") (pin "3") (pinfunction "OUT1_3") (pintype "passive"))
    )
    (net (code "31") (name "Net-(D2-K)") (class "Default")
      (node (ref "D2") (pin "2") (pinfunction "K_2") (pintype "passive"))
      (node (ref "U1") (pin "4") (pinfunction "OUT2_4") (pintype "passive"))
    )
    (net (code "32") (name "Net-(D3-K)") (class "Default")
      (node (ref "D3") (pin "2") (pinfunction "K_2") (pintype "passive"))
      (node (ref "U1") (pin "5") (pinfunction "OUT3_5") (pintype "passive"))
    )
    (net (code "33") (name "Net-(D4-K)") (class "Default")
      (node (ref "D4") (pin "2") (pinfunction "K_2") (pintype "passive"))
      (node (ref "U2") (pin "3") (pinfunction "OUT1_3") (pintype "passive"))
    )
    (net (code "34") (name "Net-(D5-K)") (class "Default")
      (node (ref "D5") (pin "2") (pinfunction "K_2") (pintype "passive"))
      (node (ref "U2") (pin "4") (pinfunction "OUT2_4") (pintype "passive"))
    )
    (net (code "35") (name "Net-(D6-K)") (class "Default")
      (node (ref "D6") (pin "2") (pinfunction "K_2") (pintype "passive"))
      (node (ref "U2") (pin "5") (pinfunction "OUT3_5") (pintype "passive"))
    )
    (net (code "36") (name "Net-(D7-A)") (class "Default")
      (node (ref "D7") (pin "1") (pinfunction "A_1") (pintype "passive"))
      (node (ref "R15") (pin "1") (pinfunction "1_1") (pintype "passive"))
    )
    (net (code "37") (name "Net-(D7-K)") (class "Default")
      (node (ref "D7") (pin "2") (pinfunction "K_2") (pintype "passive"))
      (node (ref "U3") (pin "3") (pinfunction "PC15-OSC32_OUT_3") (pintype "bidirectional"))
    )
    (net (code "38") (name "Net-(J2-Pad26)") (class "Default")
      (node (ref "J2") (pin "26") (pinfunction "26_26") (pintype "passive"))
      (node (ref "R18") (pin "2") (pinfunction "2_2") (pintype "passive"))
    )
    (net (code "39") (name "Net-(J3-Pad5)") (class "Default")
      (node (ref "J3") (pin "5") (pinfunction "5_5") (pintype "passive"))
      (node (ref "JP1") (pin "1") (pinfunction "1_1") (pintype "passive"))
    )
    (net (code "40") (name "Net-(R7-Pad2)") (class "Default")
      (node (ref "R7") (pin "2") (pinfunction "2_2") (pintype "passive"))
      (node (ref "R9") (pin "1") (pinfunction "1_1") (pintype "passive"))
      (node (ref "S5") (pin "A") (pinfunction "A_A") (pintype "passive"))
    )
    (net (code "41") (name "Net-(R10-Pad1)") (class "Default")
      (node (ref "R10") (pin "1") (pinfunction "1_1") (pintype "passive"))
      (node (ref "R6") (pin "2") (pinfunction "2_2") (pintype "passive"))
      (node (ref "S5") (pin "B") (pinfunction "B_B") (pintype "passive"))
    )
    (net (code "42") (name "Net-(U3-PB9{slash}PC14-OSC32_IN)") (class "Default")
      (node (ref "U3") (pin "2") (pinfunction "PB9/PC14-OSC32_IN_2") (pintype "bidirectional"))
      (node (ref "Y1") (pin "3") (pinfunction "OUT_3") (pintype "passive"))
    )
    (net (code "43") (name "SA0") (class "Default")
      (node (ref "J2") (pin "15") (pinfunction "15_15") (pintype "passive"))
      (node (ref "R16") (pin "1") (pinfunction "1_1") (pintype "passive"))
    )
    (net (code "44") (name "unconnected-(J2-Pad7)") (class "Default")
      (node (ref "J2") (pin "7") (pinfunction "7_7") (pintype "passive+no_connect"))
    )
    (net (code "45") (name "unconnected-(J2-Pad16)") (class "Default")
      (node (ref "J2") (pin "16") (pinfunction "16_16") (pintype "passive+no_connect"))
    )
    (net (code "46") (name "unconnected-(J2-Pad17)") (class "Default")
      (node (ref "J2") (pin "17") (pinfunction "17_17") (pintype "passive+no_connect"))
    )
    (net (code "47") (name "unconnected-(J2-Pad21)") (class "Default")
      (node (ref "J2") (pin "21") (pinfunction "21_21") (pintype "passive+no_connect"))
    )
    (net (code "48") (name "unconnected-(J2-Pad22)") (class "Default")
      (node (ref "J2") (pin "22") (pinfunction "22_22") (pintype "passive+no_connect"))
    )
    (net (code "49") (name "unconnected-(J2-Pad23)") (class "Default")
      (node (ref "J2") (pin "23") (pinfunction "23_23") (pintype "passive+no_connect"))
    )
    (net (code "50") (name "unconnected-(J2-Pad24)") (class "Default")
      (node (ref "J2") (pin "24") (pinfunction "24_24") (pintype "passive+no_connect"))
    )
    (net (code "51") (name "unconnected-(J2-Pad25)") (class "Default")
      (node (ref "J2") (pin "25") (pinfunction "25_25") (pintype "passive+no_connect"))
    )
    (net (code "52") (name "unconnected-(J2-PadS1)") (class "Default")
      (node (ref "J2") (pin "S1") (pinfunction "S1_S1") (pintype "passive+no_connect"))
    )
    (net (code "53") (name "unconnected-(J2-PadS2)") (class "Default")
      (node (ref "J2") (pin "S2") (pinfunction "S2_S2") (pintype "passive+no_connect"))
    )
    (net (code "54") (name "unconnected-(J3-Pad7)") (class "Default")
      (node (ref "J3") (pin "7") (pinfunction "7_7") (pintype "passive+no_connect"))
    )
    (net (code "55") (name "unconnected-(J3-Pad8)") (class "Default")
      (node (ref "J3") (pin "8") (pinfunction "8_8") (pintype "passive+no_connect"))
    )
    (net (code "56") (name "unconnected-(J3-Pad9)") (class "Default")
      (node (ref "J3") (pin "9") (pinfunction "9_9") (pintype "passive+no_connect"))
    )
    (net (code "57") (name "unconnected-(U1-VBM-Pad10)") (class "Default")
      (node (ref "U1") (pin "10") (pinfunction "VBM_10") (pintype "passive+no_connect"))
    )
    (net (code "58") (name "unconnected-(U2-VBM-Pad10)") (class "Default")
      (node (ref "U2") (pin "10") (pinfunction "VBM_10") (pintype "passive+no_connect"))
    )
    (net (code "59") (name "unconnected-(U3-PA3-Pad10)") (class "Default")
      (node (ref "U3") (pin "10") (pinfunction "PA3_10") (pintype "bidirectional+no_connect"))
    )
    (net (code "60") (name "unconnected-(Y1-E{slash}D-Pad1)") (class "Default")
      (node (ref "Y1") (pin "1") (pinfunction "E/D_1") (pintype "passive+no_connect"))
    )
  )
)
